# design.net
KiCad netlist of a schematic drawn in Altium Designer
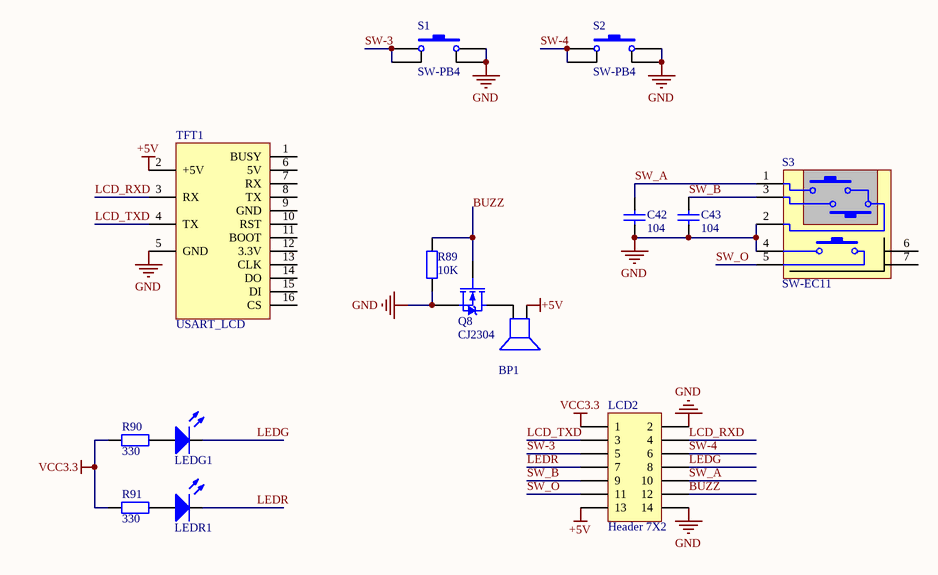
[diagram p0: 显示面板.SchDoc]

(export (version "E")
  (design (tool "Eeschema 10.0.6"))
  (components
    (comp (ref "BP1")
      (value "BUZZER")
      (footprint "蜂鸣器")
      (description "蜂鸣器")
      (libsource (lib "MY_Library") (part "BUZZER"))
    )
    (comp (ref "C42")
      (value "104")
      (footprint "C-RAD-0603")
      (description "无极性电容")
      (fields (field (name "Comment") "Cap") (field (name "PUBLISHER") "Altium Limited"))
      (libsource (lib "Fszhang") (part "Cap"))
    )
    (comp (ref "C43")
      (value "104")
      (footprint "C-RAD-0603")
      (description "无极性电容")
      (fields (field (name "Comment") "Cap") (field (name "PUBLISHER") "Altium Limited"))
      (libsource (lib "Fszhang") (part "Cap"))
    )
    (comp (ref "LCD2")
      (value "Header 7X2")
      (footprint "HDR7X2_A1")
      (description "Header, 7-Pin")
      (fields (field (name "PUBLISHER") "Altium Limited"))
      (libsource (lib "Fszhang") (part "Header 7X2"))
    )
    (comp (ref "LEDG1") (value "COLOUR") (footprint "LEDφ6") (libsource (lib "MY_Library") (part "ledφ6")))
    (comp (ref "LEDR1") (value "COLOUR") (footprint "LEDφ6") (libsource (lib "MY_Library") (part "ledφ6")))
    (comp (ref "Q8")
      (value "CJ2304")
      (footprint "SOT-23")
      (description "N-Channel MOSFET")
      (fields (field (name "PUBLISHER") "Altium Limited"))
      (libsource (lib "Fszhang") (part "MOSFET-N"))
    )
    (comp (ref "R89")
      (value "10K")
      (footprint "0603-1")
      (description "贴片电阻")
      (fields (field (name "Comment") "Res1") (field (name "PUBLISHER") "Altium Limited"))
      (libsource (lib "") (part "Res1_1"))
    )
    (comp (ref "R90")
      (value "330")
      (footprint "0603-1")
      (description "贴片电阻")
      (fields (field (name "Comment") "Res1") (field (name "PUBLISHER") "Altium Limited"))
      (libsource (lib "Fszhang") (part "Res1"))
    )
    (comp (ref "R91")
      (value "330")
      (footprint "0603-1")
      (description "贴片电阻")
      (fields (field (name "Comment") "Res1") (field (name "PUBLISHER") "Altium Limited"))
      (libsource (lib "Fszhang") (part "Res1"))
    )
    (comp (ref "S1")
      (value "SW-PB4")
      (footprint "SW_PB4_A1")
      (description "微动开关")
      (fields (field (name "PUBLISHER") "Altium Limited"))
      (libsource (lib "Fszhang") (part "SW-PB4"))
    )
    (comp (ref "S2")
      (value "SW-PB4")
      (footprint "SW_PB4_A1")
      (description "微动开关")
      (fields (field (name "PUBLISHER") "Altium Limited"))
      (libsource (lib "Fszhang") (part "SW-PB4"))
    )
    (comp (ref "S3")
      (value "SW-EC11")
      (footprint "EC11")
      (description "旋转编码开关")
      (fields (field (name "PUBLISHER") "Altium Limited"))
      (libsource (lib "Fszhang") (part "SW-EC11"))
    )
    (comp (ref "TFT1")
      (value "USART_LCD")
      (footprint "3.0寸")
      (description "usart串口屏")
      (libsource (lib "UASRT_LCD") (part "USART_LCD"))
    )
  )
  (nets
    (net (code "1") (name "+5V") (class "Default")
      (node (ref "BP1") (pin "1") (pinfunction "+_1") (pintype "passive"))
      (node (ref "LCD2") (pin "13") (pinfunction "13_13") (pintype "passive"))
      (node (ref "TFT1") (pin "2") (pinfunction "+5V_2") (pintype "passive"))
    )
    (net (code "2") (name "/BUZZ") (class "Default")
      (node (ref "LCD2") (pin "12") (pinfunction "12_12") (pintype "passive"))
      (node (ref "Q8") (pin "1") (pinfunction "G_1") (pintype "passive"))
      (node (ref "R89") (pin "2") (pinfunction "2_2") (pintype "passive"))
    )
    (net (code "3") (name "/LCD_RXD") (class "Default")
      (node (ref "LCD2") (pin "4") (pinfunction "4_4") (pintype "passive"))
      (node (ref "TFT1") (pin "3") (pinfunction "RX_3") (pintype "passive"))
    )
    (net (code "4") (name "/LCD_TXD") (class "Default")
      (node (ref "LCD2") (pin "3") (pinfunction "3_3") (pintype "passive"))
      (node (ref "TFT1") (pin "4") (pinfunction "TX_4") (pintype "passive"))
    )
    (net (code "5") (name "/LEDG") (class "Default")
      (node (ref "LCD2") (pin "8") (pinfunction "8_8") (pintype "passive"))
      (node (ref "LEDG1") (pin "2") (pinfunction "-_2") (pintype "passive"))
    )
    (net (code "6") (name "/LEDR") (class "Default")
      (node (ref "LCD2") (pin "7") (pinfunction "7_7") (pintype "passive"))
      (node (ref "LEDR1") (pin "2") (pinfunction "-_2") (pintype "passive"))
    )
    (net (code "7") (name "/SW-3") (class "Default")
      (node (ref "LCD2") (pin "5") (pinfunction "5_5") (pintype "passive"))
      (node (ref "S1") (pin "1") (pinfunction "1_1") (pintype "passive"))
      (node (ref "S1") (pin "4") (pinfunction "4_4") (pintype "passive"))
    )
    (net (code "8") (name "/SW-4") (class "Default")
      (node (ref "LCD2") (pin "6") (pinfunction "6_6") (pintype "passive"))
      (node (ref "S2") (pin "1") (pinfunction "1_1") (pintype "passive"))
      (node (ref "S2") (pin "4") (pinfunction "4_4") (pintype "passive"))
    )
    (net (code "9") (name "/SW_A") (class "Default")
      (node (ref "C42") (pin "2") (pinfunction "2_2") (pintype "passive"))
      (node (ref "LCD2") (pin "10") (pinfunction "10_10") (pintype "passive"))
      (node (ref "S3") (pin "1") (pinfunction "1_1") (pintype "passive"))
    )
    (net (code "10") (name "/SW_B") (class "Default")
      (node (ref "C43") (pin "2") (pinfunction "2_2") (pintype "passive"))
      (node (ref "LCD2") (pin "9") (pinfunction "9_9") (pintype "passive"))
      (node (ref "S3") (pin "3") (pinfunction "3_3") (pintype "passive"))
    )
    (net (code "11") (name "/SW_O") (class "Default")
      (node (ref "LCD2") (pin "11") (pinfunction "11_11") (pintype "passive"))
      (node (ref "S3") (pin "5") (pinfunction "5_5") (pintype "passive"))
    )
    (net (code "12") (name "GND") (class "Default")
      (node (ref "C42") (pin "1") (pinfunction "1_1") (pintype "passive"))
      (node (ref "C43") (pin "1") (pinfunction "1_1") (pintype "passive"))
      (node (ref "LCD2") (pin "14") (pinfunction "14_14") (pintype "passive"))
      (node (ref "LCD2") (pin "2") (pinfunction "2_2") (pintype "passive"))
      (node (ref "Q8") (pin "2") (pinfunction "S_2") (pintype "passive"))
      (node (ref "R89") (pin "1") (pinfunction "1_1") (pintype "passive"))
      (node (ref "S1") (pin "2") (pinfunction "2_2") (pintype "passive"))
      (node (ref "S1") (pin "3") (pinfunction "3_3") (pintype "passive"))
      (node (ref "S2") (pin "2") (pinfunction "2_2") (pintype "passive"))
      (node (ref "S2") (pin "3") (pinfunction "3_3") (pintype "passive"))
      (node (ref "S3") (pin "2") (pinfunction "2_2") (pintype "passive"))
      (node (ref "S3") (pin "4") (pinfunction "4_4") (pintype "passive"))
      (node (ref "TFT1") (pin "5") (pinfunction "GND_5") (pintype "passive"))
    )
    (net (code "13") (name "Net-(BP1--)") (class "Default")
      (node (ref "BP1") (pin "2") (pinfunction "-_2") (pintype "passive"))
      (node (ref "Q8") (pin "3") (pinfunction "D_3") (pintype "passive"))
    )
    (net (code "14") (name "Net-(LEDG1-+)") (class "Default")
      (node (ref "LEDG1") (pin "1") (pinfunction "+_1") (pintype "passive"))
      (node (ref "R90") (pin "1") (pinfunction "1_1") (pintype "passive"))
    )
    (net (code "15") (name "Net-(LEDR1-+)") (class "Default")
      (node (ref "LEDR1") (pin "1") (pinfunction "+_1") (pintype "passive"))
      (node (ref "R91") (pin "1") (pinfunction "1_1") (pintype "passive"))
    )
    (net (code "16") (name "VCC3.3") (class "Default")
      (node (ref "LCD2") (pin "1") (pinfunction "1_1") (pintype "passive"))
      (node (ref "R90") (pin "2") (pinfunction "2_2") (pintype "passive"))
      (node (ref "R91") (pin "2") (pinfunction "2_2") (pintype "passive"))
    )
    (net (code "17") (name "unconnected-(S3-Pad6)") (class "Default")
      (node (ref "S3") (pin "6") (pinfunction "6_6") (pintype "passive"))
    )
    (net (code "18") (name "unconnected-(S3-Pad7)") (class "Default")
      (node (ref "S3") (pin "7") (pinfunction "7_7") (pintype "passive"))
    )
    (net (code "19") (name "unconnected-(TFT1-3.3V-Pad12)") (class "Default")
      (node (ref "TFT1") (pin "12") (pinfunction "3.3V_12") (pintype "passive"))
    )
    (net (code "20") (name "unconnected-(TFT1-5V-Pad6)") (class "Default")
      (node (ref "TFT1") (pin "6") (pinfunction "5V_6") (pintype "passive"))
    )
    (net (code "21") (name "unconnected-(TFT1-BOOT-Pad11)") (class "Default")
      (node (ref "TFT1") (pin "11") (pinfunction "BOOT_11") (pintype "passive"))
    )
    (net (code "22") (name "unconnected-(TFT1-BUSY-Pad1)") (class "Default")
      (node (ref "TFT1") (pin "1") (pinfunction "BUSY_1") (pintype "passive"))
    )
    (net (code "23") (name "unconnected-(TFT1-CLK-Pad13)") (class "Default")
      (node (ref "TFT1") (pin "13") (pinfunction "CLK_13") (pintype "passive"))
    )
    (net (code "24") (name "unconnected-(TFT1-CS-Pad16)") (class "Default")
      (node (ref "TFT1") (pin "16") (pinfunction "CS_16") (pintype "passive"))
    )
    (net (code "25") (name "unconnected-(TFT1-DI-Pad15)") (class "Default")
      (node (ref "TFT1") (pin "15") (pinfunction "DI_15") (pintype "passive"))
    )
    (net (code "26") (name "unconnected-(TFT1-DO-Pad14)") (class "Default")
      (node (ref "TFT1") (pin "14") (pinfunction "DO_14") (pintype "passive"))
    )
    (net (code "27") (name "unconnected-(TFT1-GND-Pad9)") (class "Default")
      (node (ref "TFT1") (pin "9") (pinfunction "GND_9") (pintype "passive"))
    )
    (net (code "28") (name "unconnected-(TFT1-RST-Pad10)") (class "Default")
      (node (ref "TFT1") (pin "10") (pinfunction "RST_10") (pintype "passive"))
    )
    (net (code "29") (name "unconnected-(TFT1-RX-Pad7)") (class "Default")
      (node (ref "TFT1") (pin "7") (pinfunction "RX_7") (pintype "passive"))
    )
    (net (code "30") (name "unconnected-(TFT1-TX-Pad8)") (class "Default")
      (node (ref "TFT1") (pin "8") (pinfunction "TX_8") (pintype "passive"))
    )
  )
)
